# USBasp_A.net
KiCad netlist of a schematic drawn in EAGLE
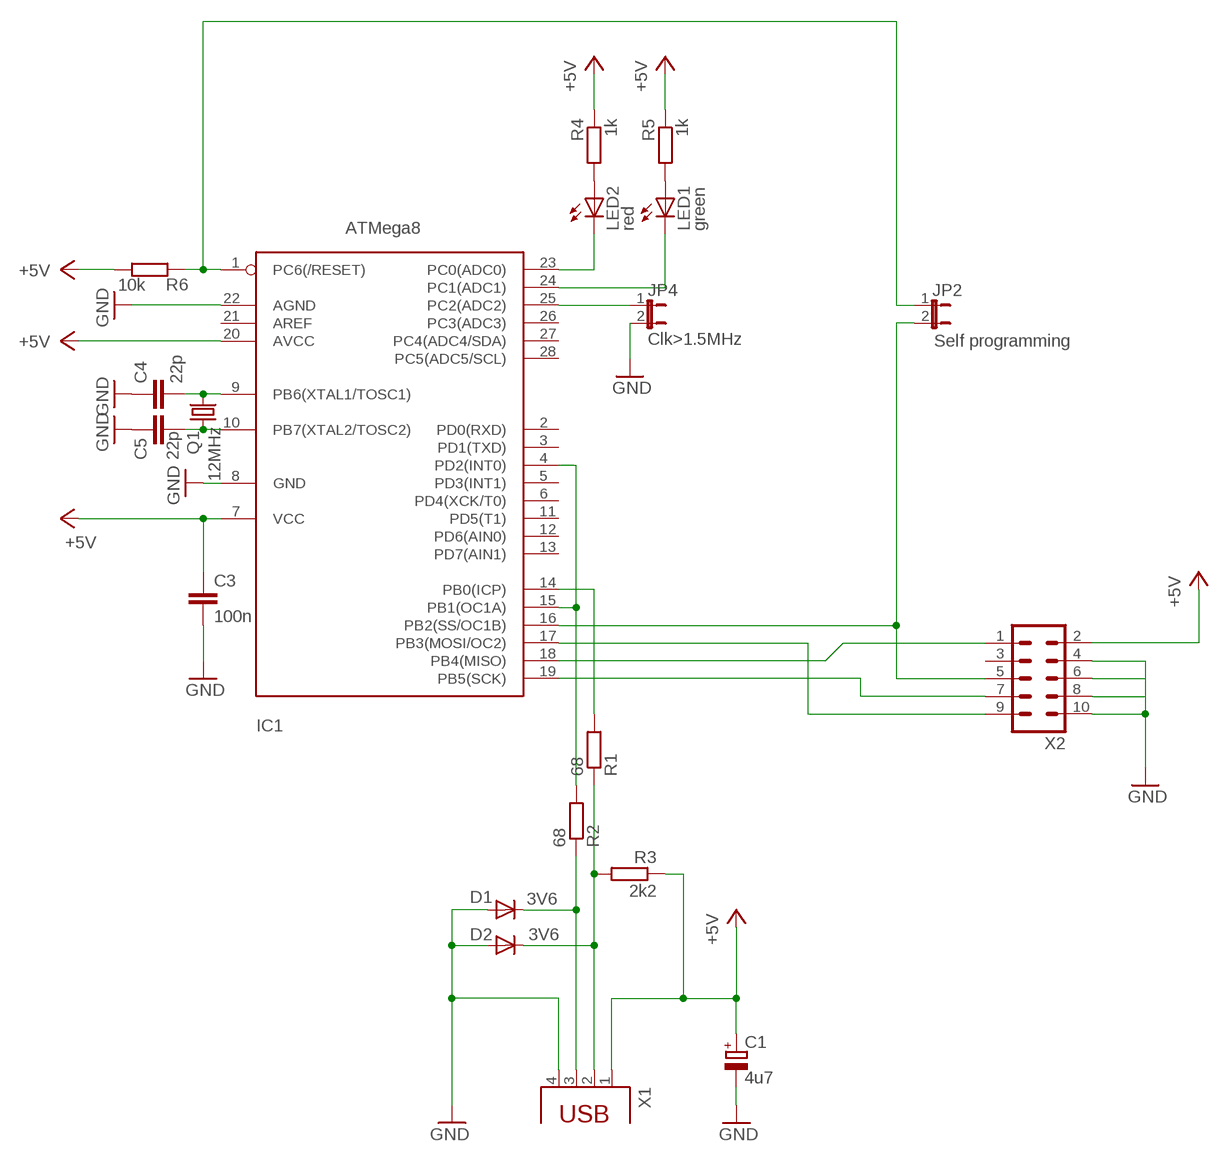
[diagram p0: schematic, sheet 1]

(export (version "E")
  (design (tool "Eeschema 10.0.6"))
  (components
    (comp (ref "C1")
      (value "4u7")
      (footprint "eagle-import:E2,5-5")
      (libsource (lib "eagle-import") (part "CPOL-EUE2.5-5"))
    )
    (comp (ref "C3")
      (value "100n")
      (footprint "eagle-import:C1206K")
      (libsource (lib "eagle-import") (part "C-EUC1206K"))
    )
    (comp (ref "C4")
      (value "22p")
      (footprint "eagle-import:C1206K")
      (libsource (lib "eagle-import") (part "C-EUC1206K"))
    )
    (comp (ref "C5")
      (value "22p")
      (footprint "eagle-import:C1206K")
      (libsource (lib "eagle-import") (part "C-EUC1206K"))
    )
    (comp (ref "D1")
      (value "3V6")
      (footprint "eagle-import:SOD80C")
      (libsource (lib "eagle-import") (part "PMLL41SOD80C"))
    )
    (comp (ref "D2")
      (value "3V6")
      (footprint "eagle-import:SOD80C")
      (libsource (lib "eagle-import") (part "PMLL41SOD80C"))
    )
    (comp (ref "IC1")
      (value "ATMega8")
      (footprint "eagle-import:DIL28-3")
      (libsource (lib "eagle-import") (part "MEGA8-P"))
    )
    (comp (ref "JP2")
      (value "Self programming")
      (footprint "eagle-import:JP1")
      (libsource (lib "eagle-import") (part "JP1E"))
    )
    (comp (ref "JP4")
      (value "Clk>1.5MHz")
      (footprint "eagle-import:JP1")
      (libsource (lib "eagle-import") (part "JP1E"))
    )
    (comp (ref "LED1")
      (value "green")
      (footprint "eagle-import:LED3MM")
      (libsource (lib "eagle-import") (part "LED3MM"))
    )
    (comp (ref "LED2")
      (value "red")
      (footprint "eagle-import:LED3MM")
      (libsource (lib "eagle-import") (part "LED3MM"))
    )
    (comp (ref "Q1")
      (value "12MHz")
      (footprint "eagle-import:HC49_S")
      (libsource (lib "eagle-import") (part "CRYTALHC49S"))
    )
    (comp (ref "R1")
      (value "68")
      (footprint "eagle-import:R1206W")
      (libsource (lib "eagle-import") (part "R-EU_R1206W"))
    )
    (comp (ref "R2")
      (value "68")
      (footprint "eagle-import:R1206W")
      (libsource (lib "eagle-import") (part "R-EU_R1206W"))
    )
    (comp (ref "R3")
      (value "2k2")
      (footprint "eagle-import:R1206W")
      (libsource (lib "eagle-import") (part "R-EU_R1206W"))
    )
    (comp (ref "R4")
      (value "1k")
      (footprint "eagle-import:R1206W")
      (libsource (lib "eagle-import") (part "R-EU_R1206W"))
    )
    (comp (ref "R5")
      (value "1k")
      (footprint "eagle-import:R1206W")
      (libsource (lib "eagle-import") (part "R-EU_R1206W"))
    )
    (comp (ref "R6")
      (value "10k")
      (footprint "eagle-import:R1206W")
      (libsource (lib "eagle-import") (part "R-EU_R1206W"))
    )
    (comp (ref "X1")
      (value "PN87520")
      (footprint "eagle-import:PN87520")
      (libsource (lib "eagle-import") (part "PN87520"))
    )
    (comp (ref "X2")
      (value "ML10")
      (footprint "eagle-import:ML10")
      (libsource (lib "eagle-import") (part "ML10"))
    )
  )
  (nets
    (net (code "1") (name "+5V") (class "Default")
      (node (ref "C1") (pin "+") (pinfunction "+_+") (pintype "passive"))
      (node (ref "C3") (pin "1") (pinfunction "1_1") (pintype "passive"))
      (node (ref "IC1") (pin "20") (pinfunction "AVCC_20") (pintype "bidirectional"))
      (node (ref "IC1") (pin "7") (pinfunction "VCC_7") (pintype "bidirectional"))
      (node (ref "R3") (pin "1") (pinfunction "1_1") (pintype "passive"))
      (node (ref "R4") (pin "1") (pinfunction "1_1") (pintype "passive"))
      (node (ref "R5") (pin "1") (pinfunction "1_1") (pintype "passive"))
      (node (ref "R6") (pin "1") (pinfunction "1_1") (pintype "passive"))
      (node (ref "X1") (pin "1") (pinfunction "1_1") (pintype "passive"))
      (node (ref "X2") (pin "2") (pinfunction "2_2") (pintype "passive"))
    )
    (net (code "2") (name "GND") (class "Default")
      (node (ref "C1") (pin "-") (pinfunction "-_-") (pintype "passive"))
      (node (ref "C3") (pin "2") (pinfunction "2_2") (pintype "passive"))
      (node (ref "C4") (pin "1") (pinfunction "1_1") (pintype "passive"))
      (node (ref "C5") (pin "1") (pinfunction "1_1") (pintype "passive"))
      (node (ref "D1") (pin "A") (pinfunction "A_A") (pintype "passive"))
      (node (ref "D2") (pin "A") (pinfunction "A_A") (pintype "passive"))
      (node (ref "IC1") (pin "22") (pinfunction "AGND_22") (pintype "bidirectional"))
      (node (ref "IC1") (pin "8") (pinfunction "GND_8") (pintype "bidirectional"))
      (node (ref "JP4") (pin "2") (pinfunction "2_2") (pintype "passive"))
      (node (ref "X1") (pin "4") (pinfunction "4_4") (pintype "passive"))
      (node (ref "X2") (pin "10") (pinfunction "10_10") (pintype "passive"))
      (node (ref "X2") (pin "4") (pinfunction "4_4") (pintype "passive"))
      (node (ref "X2") (pin "6") (pinfunction "6_6") (pintype "passive"))
      (node (ref "X2") (pin "8") (pinfunction "8_8") (pintype "passive"))
    )
    (net (code "3") (name "Net-(D1-PadC)") (class "Default")
      (node (ref "D1") (pin "C") (pinfunction "C_C") (pintype "passive"))
      (node (ref "R2") (pin "1") (pinfunction "1_1") (pintype "passive"))
      (node (ref "X1") (pin "3") (pinfunction "3_3") (pintype "passive"))
    )
    (net (code "4") (name "Net-(D2-PadC)") (class "Default")
      (node (ref "D2") (pin "C") (pinfunction "C_C") (pintype "passive"))
      (node (ref "R1") (pin "1") (pinfunction "1_1") (pintype "passive"))
      (node (ref "R3") (pin "2") (pinfunction "2_2") (pintype "passive"))
      (node (ref "X1") (pin "2") (pinfunction "2_2") (pintype "passive"))
    )
    (net (code "5") (name "Net-(IC1-PB0(ICP))") (class "Default")
      (node (ref "IC1") (pin "14") (pinfunction "PB0(ICP)_14") (pintype "bidirectional"))
      (node (ref "R1") (pin "2") (pinfunction "2_2") (pintype "passive"))
    )
    (net (code "6") (name "Net-(IC1-PB1(OC1A))") (class "Default")
      (node (ref "IC1") (pin "15") (pinfunction "PB1(OC1A)_15") (pintype "bidirectional"))
      (node (ref "IC1") (pin "4") (pinfunction "PD2(INT0)_4") (pintype "bidirectional"))
      (node (ref "R2") (pin "2") (pinfunction "2_2") (pintype "passive"))
    )
    (net (code "7") (name "Net-(IC1-PB2(SS{slash}OC1B))") (class "Default")
      (node (ref "IC1") (pin "16") (pinfunction "PB2(SS/OC1B)_16") (pintype "bidirectional"))
      (node (ref "JP2") (pin "2") (pinfunction "2_2") (pintype "passive"))
      (node (ref "X2") (pin "5") (pinfunction "5_5") (pintype "passive"))
    )
    (net (code "8") (name "Net-(IC1-PB3(MOSI{slash}OC2))") (class "Default")
      (node (ref "IC1") (pin "17") (pinfunction "PB3(MOSI/OC2)_17") (pintype "bidirectional"))
      (node (ref "X2") (pin "9") (pinfunction "9_9") (pintype "passive"))
    )
    (net (code "9") (name "Net-(IC1-PB4(MISO))") (class "Default")
      (node (ref "IC1") (pin "18") (pinfunction "PB4(MISO)_18") (pintype "bidirectional"))
      (node (ref "X2") (pin "1") (pinfunction "1_1") (pintype "passive"))
    )
    (net (code "10") (name "Net-(IC1-PB5(SCK))") (class "Default")
      (node (ref "IC1") (pin "19") (pinfunction "PB5(SCK)_19") (pintype "bidirectional"))
      (node (ref "X2") (pin "7") (pinfunction "7_7") (pintype "passive"))
    )
    (net (code "11") (name "Net-(IC1-PB6(XTAL1{slash}TOSC1))") (class "Default")
      (node (ref "C4") (pin "2") (pinfunction "2_2") (pintype "passive"))
      (node (ref "IC1") (pin "9") (pinfunction "PB6(XTAL1/TOSC1)_9") (pintype "bidirectional"))
      (node (ref "Q1") (pin "2") (pinfunction "2_2") (pintype "passive"))
    )
    (net (code "12") (name "Net-(IC1-PB7(XTAL2{slash}TOSC2))") (class "Default")
      (node (ref "C5") (pin "2") (pinfunction "2_2") (pintype "passive"))
      (node (ref "IC1") (pin "10") (pinfunction "PB7(XTAL2/TOSC2)_10") (pintype "bidirectional"))
      (node (ref "Q1") (pin "1") (pinfunction "1_1") (pintype "passive"))
    )
    (net (code "13") (name "Net-(IC1-PC0(ADC0))") (class "Default")
      (node (ref "IC1") (pin "23") (pinfunction "PC0(ADC0)_23") (pintype "bidirectional"))
      (node (ref "LED2") (pin "K") (pinfunction "C_K") (pintype "passive"))
    )
    (net (code "14") (name "Net-(IC1-PC1(ADC1))") (class "Default")
      (node (ref "IC1") (pin "24") (pinfunction "PC1(ADC1)_24") (pintype "bidirectional"))
      (node (ref "LED1") (pin "K") (pinfunction "C_K") (pintype "passive"))
    )
    (net (code "15") (name "Net-(IC1-PC2(ADC2))") (class "Default")
      (node (ref "IC1") (pin "25") (pinfunction "PC2(ADC2)_25") (pintype "bidirectional"))
      (node (ref "JP4") (pin "1") (pinfunction "1_1") (pintype "passive"))
    )
    (net (code "16") (name "Net-(IC1-PC6({slash}RESET))") (class "Default")
      (node (ref "IC1") (pin "1") (pinfunction "PC6(/RESET)_1") (pintype "bidirectional"))
      (node (ref "JP2") (pin "1") (pinfunction "1_1") (pintype "passive"))
      (node (ref "R6") (pin "2") (pinfunction "2_2") (pintype "passive"))
    )
    (net (code "17") (name "Net-(LED1-PadA)") (class "Default")
      (node (ref "LED1") (pin "A") (pinfunction "A_A") (pintype "passive"))
      (node (ref "R5") (pin "2") (pinfunction "2_2") (pintype "passive"))
    )
    (net (code "18") (name "Net-(LED2-PadA)") (class "Default")
      (node (ref "LED2") (pin "A") (pinfunction "A_A") (pintype "passive"))
      (node (ref "R4") (pin "2") (pinfunction "2_2") (pintype "passive"))
    )
    (net (code "19") (name "unconnected-(IC1-AREF-Pad21)") (class "Default")
      (node (ref "IC1") (pin "21") (pinfunction "AREF_21") (pintype "bidirectional"))
    )
    (net (code "20") (name "unconnected-(IC1-PC3(ADC3)-Pad26)") (class "Default")
      (node (ref "IC1") (pin "26") (pinfunction "PC3(ADC3)_26") (pintype "bidirectional"))
    )
    (net (code "21") (name "unconnected-(IC1-PC4(ADC4{slash}SDA)-Pad27)") (class "Default")
      (node (ref "IC1") (pin "27") (pinfunction "PC4(ADC4/SDA)_27") (pintype "bidirectional"))
    )
    (net (code "22") (name "unconnected-(IC1-PC5(ADC5{slash}SCL)-Pad28)") (class "Default")
      (node (ref "IC1") (pin "28") (pinfunction "PC5(ADC5/SCL)_28") (pintype "bidirectional"))
    )
    (net (code "23") (name "unconnected-(IC1-PD0(RXD)-Pad2)") (class "Default")
      (node (ref "IC1") (pin "2") (pinfunction "PD0(RXD)_2") (pintype "bidirectional"))
    )
    (net (code "24") (name "unconnected-(IC1-PD1(TXD)-Pad3)") (class "Default")
      (node (ref "IC1") (pin "3") (pinfunction "PD1(TXD)_3") (pintype "bidirectional"))
    )
    (net (code "25") (name "unconnected-(IC1-PD3(INT1)-Pad5)") (class "Default")
      (node (ref "IC1") (pin "5") (pinfunction "PD3(INT1)_5") (pintype "bidirectional"))
    )
    (net (code "26") (name "unconnected-(IC1-PD4(XCK{slash}T0)-Pad6)") (class "Default")
      (node (ref "IC1") (pin "6") (pinfunction "PD4(XCK/T0)_6") (pintype "bidirectional"))
    )
    (net (code "27") (name "unconnected-(IC1-PD5(T1)-Pad11)") (class "Default")
      (node (ref "IC1") (pin "11") (pinfunction "PD5(T1)_11") (pintype "bidirectional"))
    )
    (net (code "28") (name "unconnected-(IC1-PD6(AIN0)-Pad12)") (class "Default")
      (node (ref "IC1") (pin "12") (pinfunction "PD6(AIN0)_12") (pintype "bidirectional"))
    )
    (net (code "29") (name "unconnected-(IC1-PD7(AIN1)-Pad13)") (class "Default")
      (node (ref "IC1") (pin "13") (pinfunction "PD7(AIN1)_13") (pintype "bidirectional"))
    )
    (net (code "30") (name "unconnected-(X2-Pad3)") (class "Default")
      (node (ref "X2") (pin "3") (pinfunction "3_3") (pintype "passive"))
    )
  )
)
